# spinner.net
KiCad netlist of a schematic drawn in EAGLE
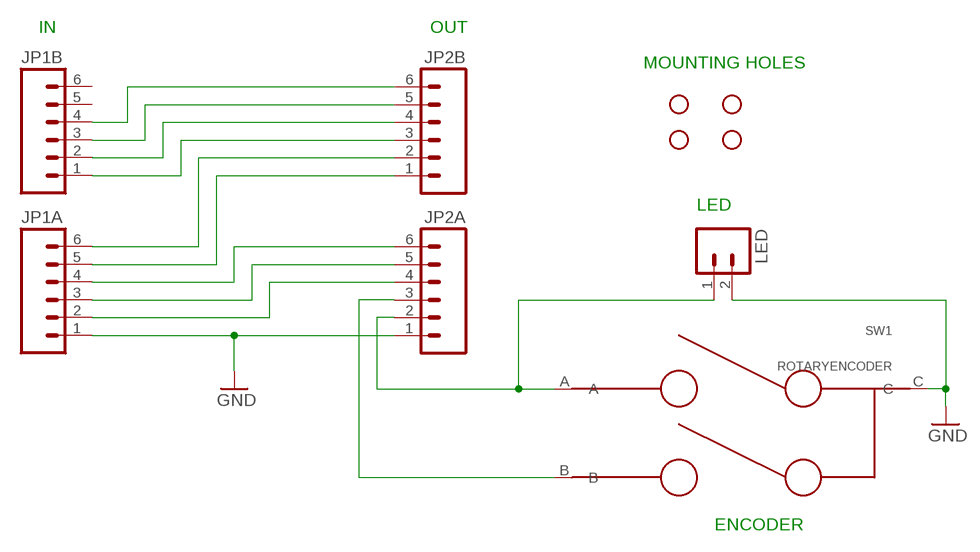
[diagram p0: schematic, sheet 1]

(export (version "E")
  (design (tool "Eeschema 10.0.6"))
  (components
    (comp (ref "JP1A")
      (value "M06LONGPADS")
      (footprint "eagle-import:1X06_LONGPADS")
      (libsource (lib "eagle-import") (part "M06LONGPADS"))
    )
    (comp (ref "JP1B")
      (value "M06LONGPADS")
      (footprint "eagle-import:1X06_LONGPADS")
      (libsource (lib "eagle-import") (part "M06LONGPADS"))
    )
    (comp (ref "JP2A")
      (value "M06LONGPADS")
      (footprint "eagle-import:1X06_LONGPADS")
      (libsource (lib "eagle-import") (part "M06LONGPADS"))
    )
    (comp (ref "JP2B")
      (value "M06LONGPADS")
      (footprint "eagle-import:1X06_LONGPADS")
      (libsource (lib "eagle-import") (part "M06LONGPADS"))
    )
    (comp (ref "JP3")
      (value "STAND-OFF")
      (footprint "eagle-import:STAND-OFF")
      (libsource (lib "eagle-import") (part "STAND-OFF"))
    )
    (comp (ref "JP4")
      (value "STAND-OFF")
      (footprint "eagle-import:STAND-OFF")
      (libsource (lib "eagle-import") (part "STAND-OFF"))
    )
    (comp (ref "JP5")
      (value "STAND-OFF")
      (footprint "eagle-import:STAND-OFF")
      (libsource (lib "eagle-import") (part "STAND-OFF"))
    )
    (comp (ref "JP6")
      (value "STAND-OFF")
      (footprint "eagle-import:STAND-OFF")
      (libsource (lib "eagle-import") (part "STAND-OFF"))
    )
    (comp (ref "LED")
      (value "M02PTH3")
      (footprint "eagle-import:1X02_LONGPADS")
      (libsource (lib "eagle-import") (part "M02PTH3"))
    )
    (comp (ref "SW1")
      (value "ROTARYENCODER")
      (footprint "eagle-import:EVQV5")
      (libsource (lib "eagle-import") (part "ROTARYENCODER"))
    )
  )
  (nets
    (net (code "1") (name "GND") (class "Default")
      (node (ref "JP1A") (pin "1") (pinfunction "1_1") (pintype "passive"))
      (node (ref "JP2A") (pin "1") (pinfunction "1_1") (pintype "passive"))
      (node (ref "LED") (pin "2") (pinfunction "2_2") (pintype "passive"))
      (node (ref "SW1") (pin "C") (pinfunction "C_C") (pintype "bidirectional"))
    )
    (net (code "2") (name "Net-(JP1A-Pad2)") (class "Default")
      (node (ref "JP1A") (pin "2") (pinfunction "2_2") (pintype "passive"))
      (node (ref "JP2A") (pin "4") (pinfunction "4_4") (pintype "passive"))
    )
    (net (code "3") (name "Net-(JP1A-Pad3)") (class "Default")
      (node (ref "JP1A") (pin "3") (pinfunction "3_3") (pintype "passive"))
      (node (ref "JP2A") (pin "5") (pinfunction "5_5") (pintype "passive"))
    )
    (net (code "4") (name "Net-(JP1A-Pad4)") (class "Default")
      (node (ref "JP1A") (pin "4") (pinfunction "4_4") (pintype "passive"))
      (node (ref "JP2A") (pin "6") (pinfunction "6_6") (pintype "passive"))
    )
    (net (code "5") (name "Net-(JP1A-Pad5)") (class "Default")
      (node (ref "JP1A") (pin "5") (pinfunction "5_5") (pintype "passive"))
      (node (ref "JP2B") (pin "1") (pinfunction "1_1") (pintype "passive"))
    )
    (net (code "6") (name "Net-(JP1A-Pad6)") (class "Default")
      (node (ref "JP1A") (pin "6") (pinfunction "6_6") (pintype "passive"))
      (node (ref "JP2B") (pin "2") (pinfunction "2_2") (pintype "passive"))
    )
    (net (code "7") (name "Net-(JP1B-Pad1)") (class "Default")
      (node (ref "JP1B") (pin "1") (pinfunction "1_1") (pintype "passive"))
      (node (ref "JP2B") (pin "3") (pinfunction "3_3") (pintype "passive"))
    )
    (net (code "8") (name "Net-(JP1B-Pad2)") (class "Default")
      (node (ref "JP1B") (pin "2") (pinfunction "2_2") (pintype "passive"))
      (node (ref "JP2B") (pin "4") (pinfunction "4_4") (pintype "passive"))
    )
    (net (code "9") (name "Net-(JP1B-Pad3)") (class "Default")
      (node (ref "JP1B") (pin "3") (pinfunction "3_3") (pintype "passive"))
      (node (ref "JP2B") (pin "5") (pinfunction "5_5") (pintype "passive"))
    )
    (net (code "10") (name "Net-(JP1B-Pad4)") (class "Default")
      (node (ref "JP1B") (pin "4") (pinfunction "4_4") (pintype "passive"))
      (node (ref "JP2B") (pin "6") (pinfunction "6_6") (pintype "passive"))
    )
    (net (code "11") (name "Net-(JP2A-Pad2)") (class "Default")
      (node (ref "JP2A") (pin "2") (pinfunction "2_2") (pintype "passive"))
      (node (ref "LED") (pin "1") (pinfunction "1_1") (pintype "passive"))
      (node (ref "SW1") (pin "A") (pinfunction "A_A") (pintype "bidirectional"))
    )
    (net (code "12") (name "Net-(JP2A-Pad3)") (class "Default")
      (node (ref "JP2A") (pin "3") (pinfunction "3_3") (pintype "passive"))
      (node (ref "SW1") (pin "B") (pinfunction "B_B") (pintype "bidirectional"))
    )
    (net (code "13") (name "unconnected-(JP1B-Pad5)") (class "Default")
      (node (ref "JP1B") (pin "5") (pinfunction "5_5") (pintype "passive"))
    )
    (net (code "14") (name "unconnected-(JP1B-Pad6)") (class "Default")
      (node (ref "JP1B") (pin "6") (pinfunction "6_6") (pintype "passive"))
    )
  )
)
